# MCU.net
KiCad netlist of a schematic drawn in Altium Designer
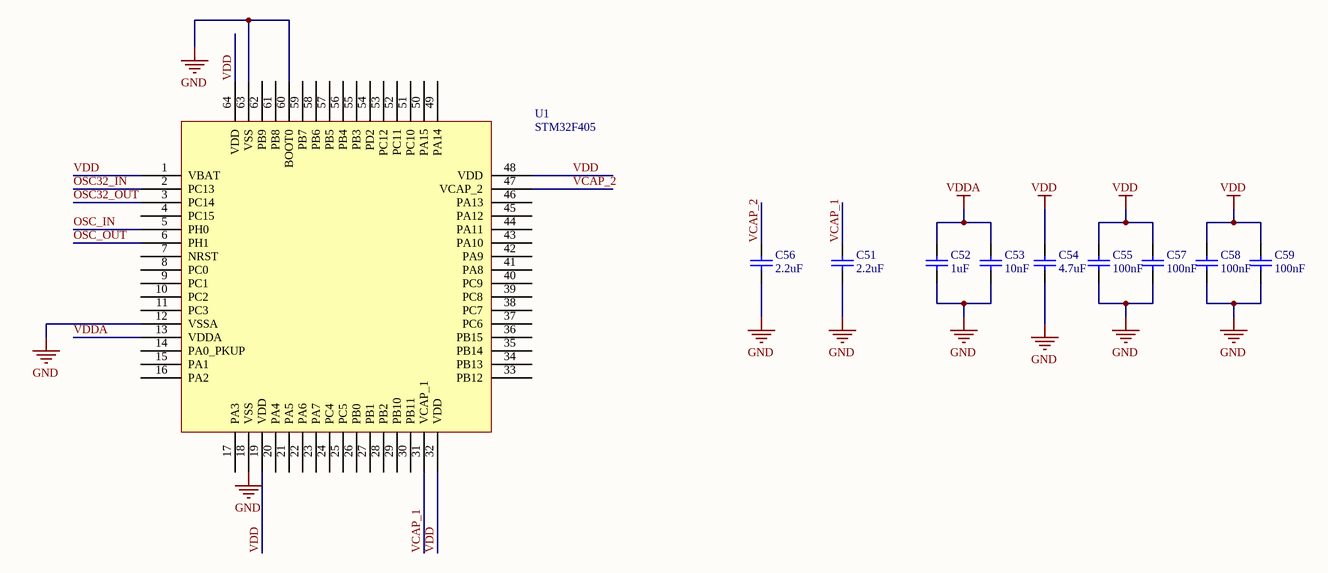
[diagram p0: MCU.SchDoc]

(export (version "E")
  (design (tool "Eeschema 10.0.6"))
  (components
    (comp (ref "C51")
      (value "2.2uF")
      (footprint "1608[0603]")
      (description "Capacitor (Semiconductor SIM Model)")
      (fields (field (name "Comment") "Cap Semi") (field (name "PUBLISHER") "Altium Limited"))
      (libsource (lib "Miscellaneous Devices") (part "Cap Semi"))
    )
    (comp (ref "C52")
      (value "1uF")
      (footprint "1608[0603]")
      (description "Capacitor (Semiconductor SIM Model)")
      (fields (field (name "Comment") "Cap Semi") (field (name "PUBLISHER") "Altium Limited"))
      (libsource (lib "Miscellaneous Devices") (part "Cap Semi"))
    )
    (comp (ref "C53")
      (value "10nF")
      (footprint "1608[0603]")
      (description "Capacitor (Semiconductor SIM Model)")
      (fields (field (name "Comment") "Cap Semi") (field (name "PUBLISHER") "Altium Limited"))
      (libsource (lib "Miscellaneous Devices") (part "Cap Semi"))
    )
    (comp (ref "C54")
      (value "4.7uF")
      (footprint "1608[0603]")
      (description "Capacitor (Semiconductor SIM Model)")
      (fields (field (name "Comment") "Cap Semi") (field (name "PUBLISHER") "Altium Limited"))
      (libsource (lib "Miscellaneous Devices") (part "Cap Semi"))
    )
    (comp (ref "C55")
      (value "100nF")
      (footprint "1608[0603]")
      (description "Capacitor (Semiconductor SIM Model)")
      (fields (field (name "Comment") "Cap Semi") (field (name "PUBLISHER") "Altium Limited"))
      (libsource (lib "Miscellaneous Devices") (part "Cap Semi"))
    )
    (comp (ref "C56")
      (value "2.2uF")
      (footprint "1608[0603]")
      (description "Capacitor (Semiconductor SIM Model)")
      (fields (field (name "Comment") "Cap Semi") (field (name "PUBLISHER") "Altium Limited"))
      (libsource (lib "Miscellaneous Devices") (part "Cap Semi"))
    )
    (comp (ref "C57")
      (value "100nF")
      (footprint "1608[0603]")
      (description "Capacitor (Semiconductor SIM Model)")
      (fields (field (name "Comment") "Cap Semi") (field (name "PUBLISHER") "Altium Limited"))
      (libsource (lib "Miscellaneous Devices") (part "Cap Semi"))
    )
    (comp (ref "C58")
      (value "100nF")
      (footprint "1608[0603]")
      (description "Capacitor (Semiconductor SIM Model)")
      (fields (field (name "Comment") "Cap Semi") (field (name "PUBLISHER") "Altium Limited"))
      (libsource (lib "Miscellaneous Devices") (part "Cap Semi"))
    )
    (comp (ref "C59")
      (value "100nF")
      (footprint "1608[0603]")
      (description "Capacitor (Semiconductor SIM Model)")
      (fields (field (name "Comment") "Cap Semi") (field (name "PUBLISHER") "Altium Limited"))
      (libsource (lib "Miscellaneous Devices") (part "Cap Semi"))
    )
    (comp (ref "U1")
      (value "STM32F405")
      (footprint "SQFP50P1200X1200-64L")
      (description "ARM Cortex-M4 32 bit Microprocessor")
      (libsource (lib "Logic_RF_Component_Symbols") (part "STM32F405RG"))
    )
  )
  (nets
    (net (code "1") (name "/OSC32_IN") (class "Default")
      (node (ref "U1") (pin "2") (pinfunction "PC13_2") (pintype "passive"))
    )
    (net (code "2") (name "/OSC32_OUT") (class "Default")
      (node (ref "U1") (pin "3") (pinfunction "PC14_3") (pintype "passive"))
    )
    (net (code "3") (name "/OSC_IN") (class "Default")
      (node (ref "U1") (pin "5") (pinfunction "PH0_5") (pintype "passive"))
    )
    (net (code "4") (name "/OSC_OUT") (class "Default")
      (node (ref "U1") (pin "6") (pinfunction "PH1_6") (pintype "passive"))
    )
    (net (code "5") (name "/VCAP_1") (class "Default")
      (node (ref "C51") (pin "2") (pinfunction "2_2") (pintype "passive"))
      (node (ref "U1") (pin "31") (pinfunction "VCAP_1_31") (pintype "passive"))
    )
    (net (code "6") (name "/VCAP_2") (class "Default")
      (node (ref "C56") (pin "2") (pinfunction "2_2") (pintype "passive"))
      (node (ref "U1") (pin "47") (pinfunction "VCAP_2_47") (pintype "passive"))
    )
    (net (code "7") (name "GND") (class "Default")
      (node (ref "C51") (pin "1") (pinfunction "1_1") (pintype "passive"))
      (node (ref "C52") (pin "1") (pinfunction "1_1") (pintype "passive"))
      (node (ref "C53") (pin "1") (pinfunction "1_1") (pintype "passive"))
      (node (ref "C54") (pin "1") (pinfunction "1_1") (pintype "passive"))
      (node (ref "C55") (pin "1") (pinfunction "1_1") (pintype "passive"))
      (node (ref "C56") (pin "1") (pinfunction "1_1") (pintype "passive"))
      (node (ref "C57") (pin "1") (pinfunction "1_1") (pintype "passive"))
      (node (ref "C58") (pin "1") (pinfunction "1_1") (pintype "passive"))
      (node (ref "C59") (pin "1") (pinfunction "1_1") (pintype "passive"))
      (node (ref "U1") (pin "12") (pinfunction "VSSA_12") (pintype "passive"))
      (node (ref "U1") (pin "18") (pinfunction "VSS_18") (pintype "passive"))
      (node (ref "U1") (pin "60") (pinfunction "BOOT0_60") (pintype "passive"))
      (node (ref "U1") (pin "63") (pinfunction "VSS_63") (pintype "passive"))
    )
    (net (code "8") (name "VDD") (class "Default")
      (node (ref "C54") (pin "2") (pinfunction "2_2") (pintype "passive"))
      (node (ref "C55") (pin "2") (pinfunction "2_2") (pintype "passive"))
      (node (ref "C57") (pin "2") (pinfunction "2_2") (pintype "passive"))
      (node (ref "C58") (pin "2") (pinfunction "2_2") (pintype "passive"))
      (node (ref "C59") (pin "2") (pinfunction "2_2") (pintype "passive"))
      (node (ref "U1") (pin "1") (pinfunction "VBAT_1") (pintype "passive"))
      (node (ref "U1") (pin "19") (pinfunction "VDD_19") (pintype "passive"))
      (node (ref "U1") (pin "32") (pinfunction "VDD_32") (pintype "passive"))
      (node (ref "U1") (pin "48") (pinfunction "VDD_48") (pintype "passive"))
      (node (ref "U1") (pin "64") (pinfunction "VDD_64") (pintype "passive"))
    )
    (net (code "9") (name "VDDA") (class "Default")
      (node (ref "C52") (pin "2") (pinfunction "2_2") (pintype "passive"))
      (node (ref "C53") (pin "2") (pinfunction "2_2") (pintype "passive"))
      (node (ref "U1") (pin "13") (pinfunction "VDDA_13") (pintype "passive"))
    )
    (net (code "10") (name "unconnected-(U1-NRST-Pad7)") (class "Default")
      (node (ref "U1") (pin "7") (pinfunction "NRST_7") (pintype "passive"))
    )
    (net (code "11") (name "unconnected-(U1-PA0_PKUP-Pad14)") (class "Default")
      (node (ref "U1") (pin "14") (pinfunction "PA0_PKUP_14") (pintype "passive"))
    )
    (net (code "12") (name "unconnected-(U1-PA1-Pad15)") (class "Default")
      (node (ref "U1") (pin "15") (pinfunction "PA1_15") (pintype "passive"))
    )
    (net (code "13") (name "unconnected-(U1-PA2-Pad16)") (class "Default")
      (node (ref "U1") (pin "16") (pinfunction "PA2_16") (pintype "passive"))
    )
    (net (code "14") (name "unconnected-(U1-PA3-Pad17)") (class "Default")
      (node (ref "U1") (pin "17") (pinfunction "PA3_17") (pintype "passive"))
    )
    (net (code "15") (name "unconnected-(U1-PA4-Pad20)") (class "Default")
      (node (ref "U1") (pin "20") (pinfunction "PA4_20") (pintype "passive"))
    )
    (net (code "16") (name "unconnected-(U1-PA5-Pad21)") (class "Default")
      (node (ref "U1") (pin "21") (pinfunction "PA5_21") (pintype "passive"))
    )
    (net (code "17") (name "unconnected-(U1-PA6-Pad22)") (class "Default")
      (node (ref "U1") (pin "22") (pinfunction "PA6_22") (pintype "passive"))
    )
    (net (code "18") (name "unconnected-(U1-PA7-Pad23)") (class "Default")
      (node (ref "U1") (pin "23") (pinfunction "PA7_23") (pintype "passive"))
    )
    (net (code "19") (name "unconnected-(U1-PA8-Pad41)") (class "Default")
      (node (ref "U1") (pin "41") (pinfunction "PA8_41") (pintype "passive"))
    )
    (net (code "20") (name "unconnected-(U1-PA9-Pad42)") (class "Default")
      (node (ref "U1") (pin "42") (pinfunction "PA9_42") (pintype "passive"))
    )
    (net (code "21") (name "unconnected-(U1-PA10-Pad43)") (class "Default")
      (node (ref "U1") (pin "43") (pinfunction "PA10_43") (pintype "passive"))
    )
    (net (code "22") (name "unconnected-(U1-PA11-Pad44)") (class "Default")
      (node (ref "U1") (pin "44") (pinfunction "PA11_44") (pintype "passive"))
    )
    (net (code "23") (name "unconnected-(U1-PA12-Pad45)") (class "Default")
      (node (ref "U1") (pin "45") (pinfunction "PA12_45") (pintype "passive"))
    )
    (net (code "24") (name "unconnected-(U1-PA13-Pad46)") (class "Default")
      (node (ref "U1") (pin "46") (pinfunction "PA13_46") (pintype "passive"))
    )
    (net (code "25") (name "unconnected-(U1-PA14-Pad49)") (class "Default")
      (node (ref "U1") (pin "49") (pinfunction "PA14_49") (pintype "passive"))
    )
    (net (code "26") (name "unconnected-(U1-PA15-Pad50)") (class "Default")
      (node (ref "U1") (pin "50") (pinfunction "PA15_50") (pintype "passive"))
    )
    (net (code "27") (name "unconnected-(U1-PB0-Pad26)") (class "Default")
      (node (ref "U1") (pin "26") (pinfunction "PB0_26") (pintype "passive"))
    )
    (net (code "28") (name "unconnected-(U1-PB1-Pad27)") (class "Default")
      (node (ref "U1") (pin "27") (pinfunction "PB1_27") (pintype "passive"))
    )
    (net (code "29") (name "unconnected-(U1-PB2-Pad28)") (class "Default")
      (node (ref "U1") (pin "28") (pinfunction "PB2_28") (pintype "passive"))
    )
    (net (code "30") (name "unconnected-(U1-PB3-Pad55)") (class "Default")
      (node (ref "U1") (pin "55") (pinfunction "PB3_55") (pintype "passive"))
    )
    (net (code "31") (name "unconnected-(U1-PB4-Pad56)") (class "Default")
      (node (ref "U1") (pin "56") (pinfunction "PB4_56") (pintype "passive"))
    )
    (net (code "32") (name "unconnected-(U1-PB5-Pad57)") (class "Default")
      (node (ref "U1") (pin "57") (pinfunction "PB5_57") (pintype "passive"))
    )
    (net (code "33") (name "unconnected-(U1-PB6-Pad58)") (class "Default")
      (node (ref "U1") (pin "58") (pinfunction "PB6_58") (pintype "passive"))
    )
    (net (code "34") (name "unconnected-(U1-PB7-Pad59)") (class "Default")
      (node (ref "U1") (pin "59") (pinfunction "PB7_59") (pintype "passive"))
    )
    (net (code "35") (name "unconnected-(U1-PB8-Pad61)") (class "Default")
      (node (ref "U1") (pin "61") (pinfunction "PB8_61") (pintype "passive"))
    )
    (net (code "36") (name "unconnected-(U1-PB9-Pad62)") (class "Default")
      (node (ref "U1") (pin "62") (pinfunction "PB9_62") (pintype "passive"))
    )
    (net (code "37") (name "unconnected-(U1-PB10-Pad29)") (class "Default")
      (node (ref "U1") (pin "29") (pinfunction "PB10_29") (pintype "passive"))
    )
    (net (code "38") (name "unconnected-(U1-PB11-Pad30)") (class "Default")
      (node (ref "U1") (pin "30") (pinfunction "PB11_30") (pintype "passive"))
    )
    (net (code "39") (name "unconnected-(U1-PB12-Pad33)") (class "Default")
      (node (ref "U1") (pin "33") (pinfunction "PB12_33") (pintype "passive"))
    )
    (net (code "40") (name "unconnected-(U1-PB13-Pad34)") (class "Default")
      (node (ref "U1") (pin "34") (pinfunction "PB13_34") (pintype "passive"))
    )
    (net (code "41") (name "unconnected-(U1-PB14-Pad35)") (class "Default")
      (node (ref "U1") (pin "35") (pinfunction "PB14_35") (pintype "passive"))
    )
    (net (code "42") (name "unconnected-(U1-PB15-Pad36)") (class "Default")
      (node (ref "U1") (pin "36") (pinfunction "PB15_36") (pintype "passive"))
    )
    (net (code "43") (name "unconnected-(U1-PC0-Pad8)") (class "Default")
      (node (ref "U1") (pin "8") (pinfunction "PC0_8") (pintype "passive"))
    )
    (net (code "44") (name "unconnected-(U1-PC1-Pad9)") (class "Default")
      (node (ref "U1") (pin "9") (pinfunction "PC1_9") (pintype "passive"))
    )
    (net (code "45") (name "unconnected-(U1-PC2-Pad10)") (class "Default")
      (node (ref "U1") (pin "10") (pinfunction "PC2_10") (pintype "passive"))
    )
    (net (code "46") (name "unconnected-(U1-PC3-Pad11)") (class "Default")
      (node (ref "U1") (pin "11") (pinfunction "PC3_11") (pintype "passive"))
    )
    (net (code "47") (name "unconnected-(U1-PC4-Pad24)") (class "Default")
      (node (ref "U1") (pin "24") (pinfunction "PC4_24") (pintype "passive"))
    )
    (net (code "48") (name "unconnected-(U1-PC5-Pad25)") (class "Default")
      (node (ref "U1") (pin "25") (pinfunction "PC5_25") (pintype "passive"))
    )
    (net (code "49") (name "unconnected-(U1-PC6-Pad37)") (class "Default")
      (node (ref "U1") (pin "37") (pinfunction "PC6_37") (pintype "passive"))
    )
    (net (code "50") (name "unconnected-(U1-PC7-Pad38)") (class "Default")
      (node (ref "U1") (pin "38") (pinfunction "PC7_38") (pintype "passive"))
    )
    (net (code "51") (name "unconnected-(U1-PC8-Pad39)") (class "Default")
      (node (ref "U1") (pin "39") (pinfunction "PC8_39") (pintype "passive"))
    )
    (net (code "52") (name "unconnected-(U1-PC9-Pad40)") (class "Default")
      (node (ref "U1") (pin "40") (pinfunction "PC9_40") (pintype "passive"))
    )
    (net (code "53") (name "unconnected-(U1-PC10-Pad51)") (class "Default")
      (node (ref "U1") (pin "51") (pinfunction "PC10_51") (pintype "passive"))
    )
    (net (code "54") (name "unconnected-(U1-PC11-Pad52)") (class "Default")
      (node (ref "U1") (pin "52") (pinfunction "PC11_52") (pintype "passive"))
    )
    (net (code "55") (name "unconnected-(U1-PC12-Pad53)") (class "Default")
      (node (ref "U1") (pin "53") (pinfunction "PC12_53") (pintype "passive"))
    )
    (net (code "56") (name "unconnected-(U1-PC15-Pad4)") (class "Default")
      (node (ref "U1") (pin "4") (pinfunction "PC15_4") (pintype "passive"))
    )
    (net (code "57") (name "unconnected-(U1-PD2-Pad54)") (class "Default")
      (node (ref "U1") (pin "54") (pinfunction "PD2_54") (pintype "passive"))
    )
  )
)
